# EEZ_SMPS_pre-regulator_r1B1.net
KiCad netlist of a schematic drawn in EAGLE
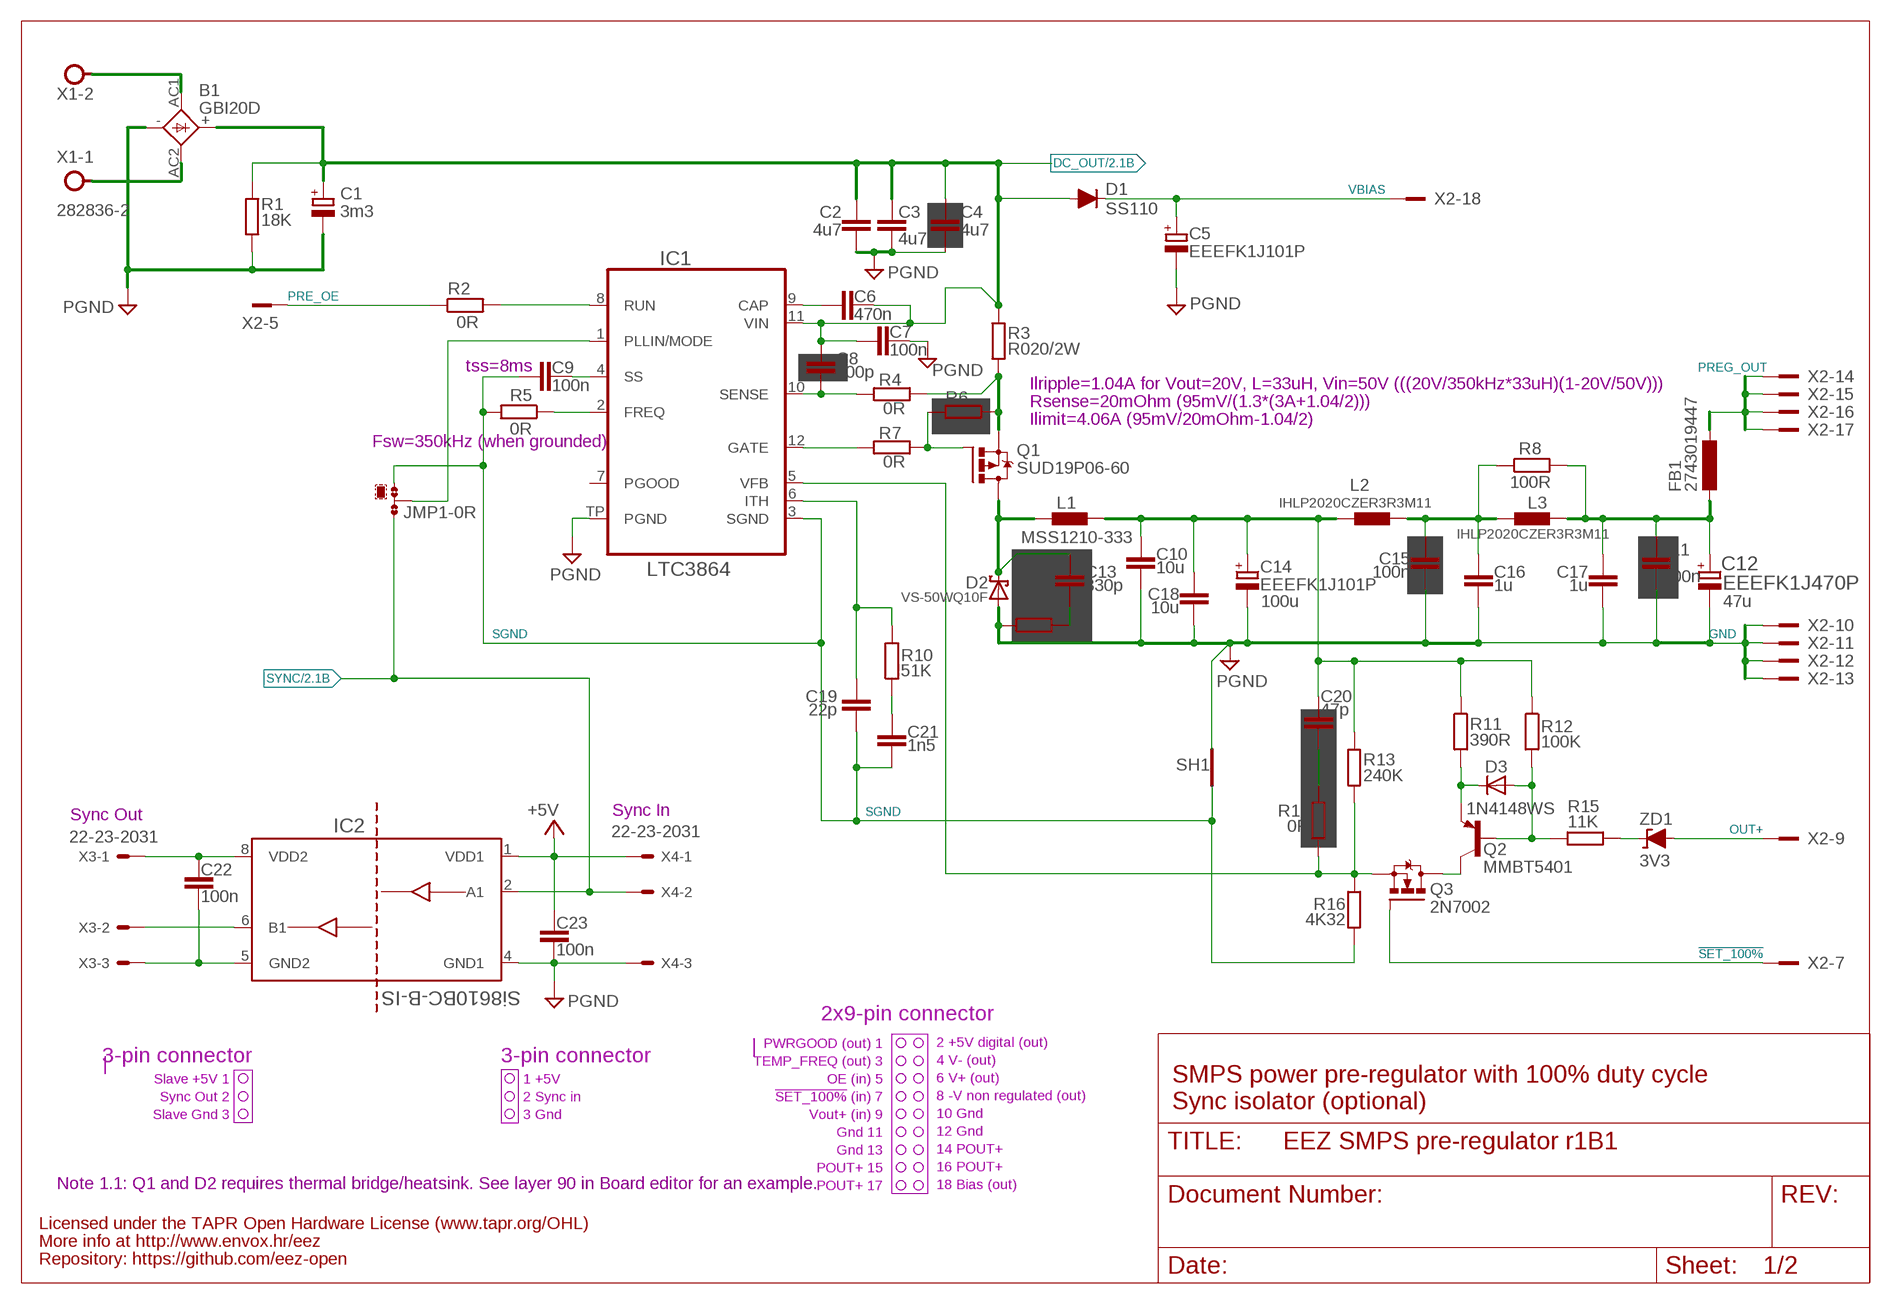
[diagram p0: schematic, sheet 1]
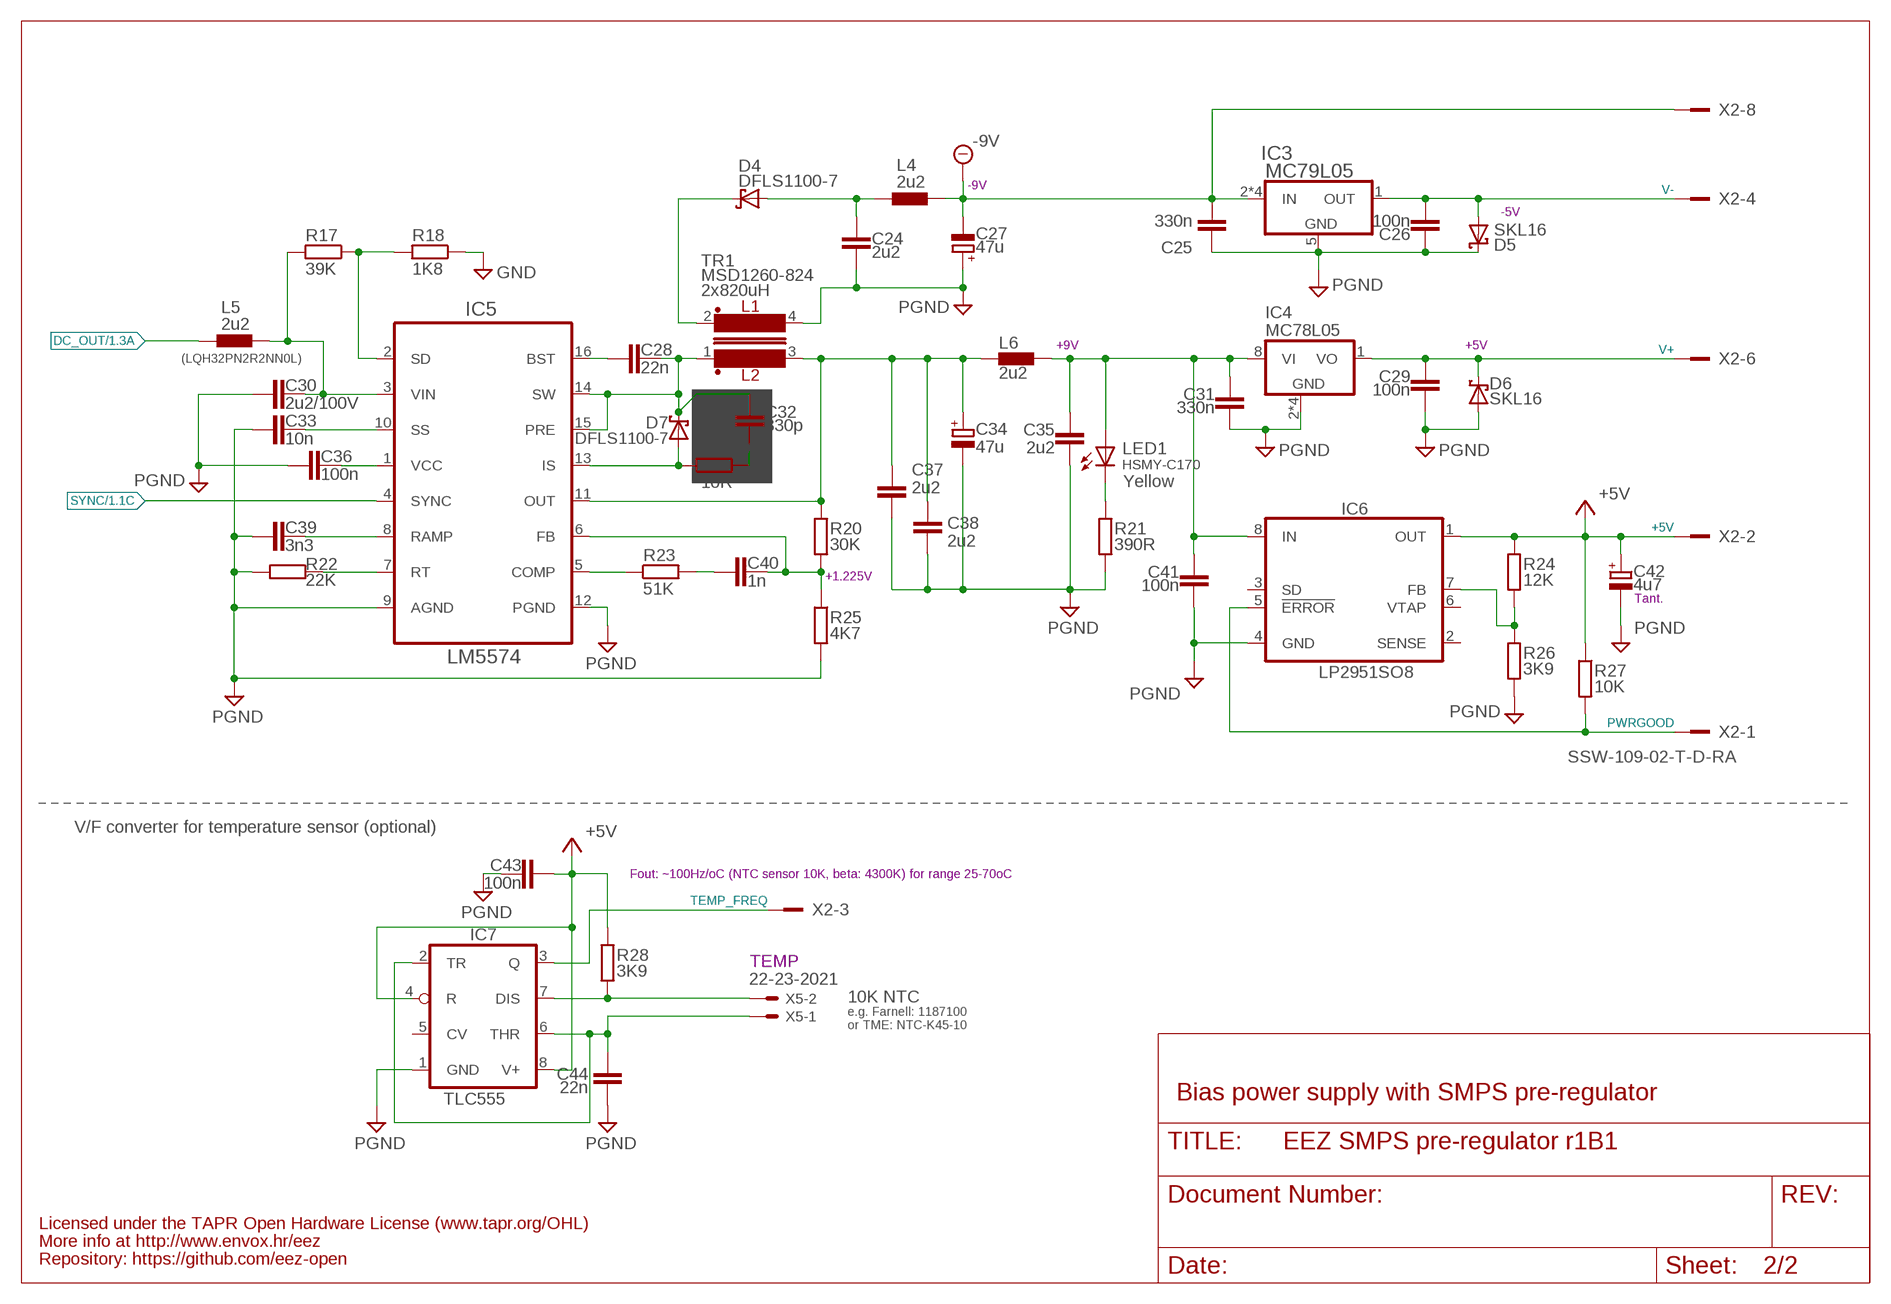
[diagram p1: schematic, sheet 2]

(export (version "E")
  (design (tool "Eeschema 10.0.6"))
  (components
    (comp (ref "C24")
      (value "2u2")
      (footprint "eagle-import:C0805")
      (libsource (lib "eagle-import") (part "C-EUC0805"))
    )
    (comp (ref "C25")
      (value "330n")
      (footprint "eagle-import:C0805")
      (libsource (lib "eagle-import") (part "C-EUC0805"))
    )
    (comp (ref "C26")
      (value "100n")
      (footprint "eagle-import:C0805")
      (libsource (lib "eagle-import") (part "C-EUC0805"))
    )
    (comp (ref "C27")
      (value "47u")
      (footprint "eagle-import:CAPAE660X610N")
      (libsource (lib "eagle-import") (part "ECAPPANASONIC_H"))
    )
    (comp (ref "C28")
      (value "22n")
      (footprint "eagle-import:C0805")
      (libsource (lib "eagle-import") (part "C-EUC0805"))
    )
    (comp (ref "C29")
      (value "100n")
      (footprint "eagle-import:C0805")
      (libsource (lib "eagle-import") (part "C-EUC0805"))
    )
    (comp (ref "C30")
      (value "2u2/100V")
      (footprint "eagle-import:C1210")
      (libsource (lib "eagle-import") (part "C-EUC1210"))
    )
    (comp (ref "C31")
      (value "330n")
      (footprint "eagle-import:C0805")
      (libsource (lib "eagle-import") (part "C-EUC0805"))
    )
    (comp (ref "C32")
      (value "330p")
      (footprint "eagle-import:C0805")
      (libsource (lib "eagle-import") (part "C-EUC0805"))
    )
    (comp (ref "C33")
      (value "10n")
      (footprint "eagle-import:C0805")
      (libsource (lib "eagle-import") (part "C-EUC0805"))
    )
    (comp (ref "C34")
      (value "47u")
      (footprint "eagle-import:CAPAE660X610N")
      (libsource (lib "eagle-import") (part "ECAPPANASONIC_H"))
    )
    (comp (ref "C35")
      (value "2u2")
      (footprint "eagle-import:C0805")
      (libsource (lib "eagle-import") (part "C-EUC0805"))
    )
    (comp (ref "C36")
      (value "100n")
      (footprint "eagle-import:C0805")
      (libsource (lib "eagle-import") (part "C-EUC0805"))
    )
    (comp (ref "C37")
      (value "2u2")
      (footprint "eagle-import:C0805")
      (libsource (lib "eagle-import") (part "C-EUC0805"))
    )
    (comp (ref "C38")
      (value "2u2")
      (footprint "eagle-import:C0805")
      (libsource (lib "eagle-import") (part "C-EUC0805"))
    )
    (comp (ref "C39")
      (value "3n3")
      (footprint "eagle-import:C0805")
      (libsource (lib "eagle-import") (part "C-EUC0805"))
    )
    (comp (ref "C40")
      (value "1n")
      (footprint "eagle-import:C0805")
      (libsource (lib "eagle-import") (part "C-EUC0805"))
    )
    (comp (ref "C41")
      (value "100n")
      (footprint "eagle-import:C0805")
      (libsource (lib "eagle-import") (part "C-EUC0805"))
    )
    (comp (ref "C42")
      (value "4u7")
      (footprint "eagle-import:EC1206")
      (libsource (lib "eagle-import") (part "ECAP1206"))
    )
    (comp (ref "C43")
      (value "100n")
      (footprint "eagle-import:C0603")
      (libsource (lib "eagle-import") (part "C-EUC0603"))
    )
    (comp (ref "C44")
      (value "22n")
      (footprint "eagle-import:C0805")
      (libsource (lib "eagle-import") (part "C-EUC0805"))
    )
    (comp (ref "D4")
      (value "DFLS1100-7")
      (footprint "eagle-import:SOD123")
      (libsource (lib "eagle-import") (part "SCHOTTKYSOD123"))
    )
    (comp (ref "D5")
      (value "SKL16")
      (footprint "eagle-import:SOD123")
      (libsource (lib "eagle-import") (part "SCHOTTKYSOD123"))
    )
    (comp (ref "D6")
      (value "SKL16")
      (footprint "eagle-import:SOD123")
      (libsource (lib "eagle-import") (part "SCHOTTKYSOD123"))
    )
    (comp (ref "D7")
      (value "DFLS1100-7")
      (footprint "eagle-import:SOD123")
      (libsource (lib "eagle-import") (part "SCHOTTKYSOD123"))
    )
    (comp (ref "IC3")
      (value "MC79L05")
      (footprint "eagle-import:SOIC127P600X173-8N")
      (libsource (lib "eagle-import") (part "MC79LXXSOIC"))
    )
    (comp (ref "IC4")
      (value "MC78L05")
      (footprint "eagle-import:SOIC127P600X173-8N")
      (libsource (lib "eagle-import") (part "MC78LXXSOIC8"))
    )
    (comp (ref "IC5")
      (value "LM5574")
      (footprint "eagle-import:SOP65P640X110-16N")
      (fields (field (name "MPN") "LM5574MT"))
      (libsource (lib "eagle-import") (part "LM5574"))
    )
    (comp (ref "IC6")
      (value "LP2951SO8")
      (footprint "eagle-import:SOIC127P600X175-8N")
      (libsource (lib "eagle-import") (part "LP2951SO8"))
    )
    (comp (ref "IC7")
      (value "TLC555")
      (footprint "eagle-import:SOIC127P600X175-8N")
      (libsource (lib "eagle-import") (part "LM555SOIC8"))
    )
    (comp (ref "L4")
      (value "2u2")
      (footprint "eagle-import:L1210")
      (libsource (lib "eagle-import") (part "L1210"))
    )
    (comp (ref "L5")
      (value "2u2")
      (footprint "eagle-import:L1210")
      (libsource (lib "eagle-import") (part "L1210"))
    )
    (comp (ref "L6")
      (value "2u2")
      (footprint "eagle-import:L1210")
      (libsource (lib "eagle-import") (part "L1210"))
    )
    (comp (ref "LED1")
      (value "HSMY-C170")
      (footprint "eagle-import:CHIPLED_0805")
      (libsource (lib "eagle-import") (part "LEDCHIPLED_0805"))
    )
    (comp (ref "R17")
      (value "39K")
      (footprint "eagle-import:R0805")
      (libsource (lib "eagle-import") (part "R-EU_R0805"))
    )
    (comp (ref "R18")
      (value "1K8")
      (footprint "eagle-import:R0805")
      (libsource (lib "eagle-import") (part "R-EU_R0805"))
    )
    (comp (ref "R19")
      (value "10R")
      (footprint "eagle-import:R1206")
      (libsource (lib "eagle-import") (part "R-EU_R1206"))
    )
    (comp (ref "R20")
      (value "30K")
      (footprint "eagle-import:R0805")
      (libsource (lib "eagle-import") (part "R-EU_R0805"))
    )
    (comp (ref "R21")
      (value "390R")
      (footprint "eagle-import:R0805")
      (libsource (lib "eagle-import") (part "R-EU_R0805"))
    )
    (comp (ref "R22")
      (value "22K")
      (footprint "eagle-import:R0805")
      (libsource (lib "eagle-import") (part "R-EU_R0805"))
    )
    (comp (ref "R23")
      (value "51K")
      (footprint "eagle-import:R0805")
      (libsource (lib "eagle-import") (part "R-EU_R0805"))
    )
    (comp (ref "R24")
      (value "12K")
      (footprint "eagle-import:R0805")
      (libsource (lib "eagle-import") (part "R-EU_R0805"))
    )
    (comp (ref "R25")
      (value "4K7")
      (footprint "eagle-import:R0805")
      (libsource (lib "eagle-import") (part "R-EU_R0805"))
    )
    (comp (ref "R26")
      (value "3K9")
      (footprint "eagle-import:R0805")
      (libsource (lib "eagle-import") (part "R-EU_R0805"))
    )
    (comp (ref "R27")
      (value "10K")
      (footprint "eagle-import:R0805")
      (libsource (lib "eagle-import") (part "R-EU_R0805"))
    )
    (comp (ref "R28")
      (value "3K9")
      (footprint "eagle-import:R0805")
      (libsource (lib "eagle-import") (part "R-EU_R0805"))
    )
    (comp (ref "TR1")
      (value "MSD1260-824")
      (footprint "eagle-import:MSD1260")
      (libsource (lib "eagle-import") (part "COILCRAFT_MSD1260INV"))
    )
    (comp (ref "X2")
      (value "SSW-109-02-T-D-RA")
      (footprint "eagle-import:SSW-109-02-T-D-RA")
      (libsource (lib "eagle-import") (part "SSW-109-02-T-D-RA"))
    )
    (comp (ref "X5")
      (value "22-23-2021")
      (footprint "eagle-import:22-23-2021")
      (fields (field (name "MF") "MOLEX"))
      (libsource (lib "eagle-import") (part "22-23-2021"))
    )
    (comp (ref "B1")
      (value "GBI20D")
      (footprint "eagle-import:GBI20")
      (libsource (lib "eagle-import") (part "BRIDGEDIOTEC"))
    )
    (comp (ref "C1")
      (value "3m3")
      (footprint "eagle-import:ECAP10_22.5")
      (libsource (lib "eagle-import") (part "ECAP10G_22.5MM"))
    )
    (comp (ref "C2")
      (value "4u7")
      (footprint "eagle-import:C1210")
      (libsource (lib "eagle-import") (part "C-EUC1210"))
    )
    (comp (ref "C3")
      (value "4u7")
      (footprint "eagle-import:C1210")
      (libsource (lib "eagle-import") (part "C-EUC1210"))
    )
    (comp (ref "C4")
      (value "4u7")
      (footprint "eagle-import:C1210")
      (libsource (lib "eagle-import") (part "C-EUC1210"))
    )
    (comp (ref "C5")
      (value "EEEFK1J101P")
      (footprint "eagle-import:ECAP5_10.5+PANASONIC_F")
      (libsource (lib "eagle-import") (part "ECAP5G_10.5MM_F"))
    )
    (comp (ref "C6")
      (value "470n")
      (footprint "eagle-import:C0805")
      (libsource (lib "eagle-import") (part "C-EUC0805"))
    )
    (comp (ref "C7")
      (value "100n")
      (footprint "eagle-import:C0805")
      (libsource (lib "eagle-import") (part "C-EUC0805"))
    )
    (comp (ref "C8")
      (value "100p")
      (footprint "eagle-import:C0805")
      (libsource (lib "eagle-import") (part "C-EUC0805"))
    )
    (comp (ref "C9")
      (value "100n")
      (footprint "eagle-import:C0805")
      (libsource (lib "eagle-import") (part "C-EUC0805"))
    )
    (comp (ref "C10")
      (value "10u")
      (footprint "eagle-import:C1210")
      (libsource (lib "eagle-import") (part "C-EUC1210"))
    )
    (comp (ref "C11")
      (value "100n")
      (footprint "eagle-import:C0805")
      (libsource (lib "eagle-import") (part "C-EUC0805"))
    )
    (comp (ref "C12")
      (value "EEEFK1J470P")
      (footprint "eagle-import:CAPAE830X1050N")
      (fields (field (name "MPN") "EEE-FK1J470P") (field (name "TOLERANCE") "±20 %"))
      (libsource (lib "eagle-import") (part "EEE--CASE-FFK1J470P"))
    )
    (comp (ref "C13")
      (value "330p")
      (footprint "eagle-import:C0805")
      (libsource (lib "eagle-import") (part "C-EUC0805"))
    )
    (comp (ref "C14")
      (value "EEEFK1J101P")
      (footprint "eagle-import:ECAP5_10.5+PANASONIC_F")
      (libsource (lib "eagle-import") (part "ECAP5G_10.5MM_F"))
    )
    (comp (ref "C15")
      (value "100n")
      (footprint "eagle-import:C0805")
      (libsource (lib "eagle-import") (part "C-EUC0805"))
    )
    (comp (ref "C16")
      (value "1u")
      (footprint "eagle-import:C1206")
      (libsource (lib "eagle-import") (part "C-EUC1206"))
    )
    (comp (ref "C17")
      (value "1u")
      (footprint "eagle-import:C1206")
      (libsource (lib "eagle-import") (part "C-EUC1206"))
    )
    (comp (ref "C18")
      (value "10u")
      (footprint "eagle-import:C1210")
      (libsource (lib "eagle-import") (part "C-EUC1210"))
    )
    (comp (ref "C19")
      (value "22p")
      (footprint "eagle-import:C0805")
      (libsource (lib "eagle-import") (part "C-EUC0805"))
    )
    (comp (ref "C20")
      (value "47p")
      (footprint "eagle-import:C0805")
      (libsource (lib "eagle-import") (part "C-EUC0805"))
    )
    (comp (ref "C21")
      (value "1n5")
      (footprint "eagle-import:C0805")
      (libsource (lib "eagle-import") (part "C-EUC0805"))
    )
    (comp (ref "C22")
      (value "100n")
      (footprint "eagle-import:C0603")
      (libsource (lib "eagle-import") (part "C-EUC0603"))
    )
    (comp (ref "C23")
      (value "100n")
      (footprint "eagle-import:C0603")
      (libsource (lib "eagle-import") (part "C-EUC0603"))
    )
    (comp (ref "D1")
      (value "SS110")
      (footprint "eagle-import:DO214AA")
      (libsource (lib "eagle-import") (part "DIODEDO214AA"))
    )
    (comp (ref "D2")
      (value "VS-50WQ10F")
      (footprint "eagle-import:TO252@1")
      (libsource (lib "eagle-import") (part "SCHOTTKYTO252"))
    )
    (comp (ref "D3")
      (value "1N4148WS")
      (footprint "eagle-import:SOD323-W")
      (libsource (lib "eagle-import") (part "DIODE-SOD323-W"))
    )
    (comp (ref "FB1")
      (value "2743019447")
      (footprint "eagle-import:L1812")
      (libsource (lib "eagle-import") (part "L-EUL1812"))
    )
    (comp (ref "IC1")
      (value "LTC3864")
      (footprint "eagle-import:LTC_05-08-1666")
      (libsource (lib "eagle-import") (part "LTC3864"))
    )
    (comp (ref "IC2")
      (value "Si8610BC-B-IS")
      (footprint "eagle-import:SOIC127P600X173-8N")
      (libsource (lib "eagle-import") (part "SI8610"))
    )
    (comp (ref "JMP1")
      (value "0R-JUMPA")
      (footprint "eagle-import:A0R-JMP")
      (libsource (lib "eagle-import") (part "0R-JUMPA"))
    )
    (comp (ref "L1")
      (value "MSS1210-333")
      (footprint "eagle-import:MSS1210")
      (libsource (lib "eagle-import") (part "COILCRAFT_MSS1210"))
    )
    (comp (ref "L2")
      (value "IHLP2020CZER3R3M11")
      (footprint "eagle-import:IHLP-2020BZ-11")
      (libsource (lib "eagle-import") (part "IHLP-2020BZ-11"))
    )
    (comp (ref "L3")
      (value "IHLP2020CZER3R3M11")
      (footprint "eagle-import:IHLP-2020BZ-11")
      (libsource (lib "eagle-import") (part "IHLP-2020BZ-11"))
    )
    (comp (ref "Q1")
      (value "SUD19P06-60")
      (footprint "eagle-import:TO229P990X239-3N")
      (libsource (lib "eagle-import") (part "P-MOSFETDPAK"))
    )
    (comp (ref "Q2")
      (value "MMBT5401")
      (footprint "eagle-import:SOT23-BEC")
      (libsource (lib "eagle-import") (part "-PNP-SOT23-BECBC857B"))
    )
    (comp (ref "Q3")
      (value "2N7002")
      (footprint "eagle-import:SOT103P240X110-3N")
      (fields (field (name "MPN") "2N7002-7-F"))
      (libsource (lib "eagle-import") (part "2N7002"))
    )
    (comp (ref "R1")
      (value "18K")
      (footprint "eagle-import:R1206")
      (libsource (lib "eagle-import") (part "R-EU_R1206"))
    )
    (comp (ref "R2")
      (value "0R")
      (footprint "eagle-import:R0805")
      (libsource (lib "eagle-import") (part "R-EU_R0805"))
    )
    (comp (ref "R3")
      (value "R020/2W")
      (footprint "eagle-import:R2512")
      (libsource (lib "eagle-import") (part "R-EU_R2512"))
    )
    (comp (ref "R4")
      (value "0R")
      (footprint "eagle-import:R0805")
      (libsource (lib "eagle-import") (part "R-EU_R0805"))
    )
    (comp (ref "R5")
      (value "0R")
      (footprint "eagle-import:R0805")
      (libsource (lib "eagle-import") (part "R-EU_R0805"))
    )
    (comp (ref "R6")
      (value "100K")
      (footprint "eagle-import:R0805")
      (libsource (lib "eagle-import") (part "R-EU_R0805"))
    )
    (comp (ref "R7")
      (value "0R")
      (footprint "eagle-import:R0805")
      (libsource (lib "eagle-import") (part "R-EU_R0805"))
    )
    (comp (ref "R8")
      (value "100R")
      (footprint "eagle-import:R0805")
      (libsource (lib "eagle-import") (part "R-EU_R0805"))
    )
    (comp (ref "R9")
      (value "10R")
      (footprint "eagle-import:R1206")
      (libsource (lib "eagle-import") (part "R-EU_R1206"))
    )
    (comp (ref "R10")
      (value "51K")
      (footprint "eagle-import:R0805")
      (libsource (lib "eagle-import") (part "R-EU_R0805"))
    )
    (comp (ref "R11")
      (value "390R")
      (footprint "eagle-import:R0805")
      (libsource (lib "eagle-import") (part "R-EU_R0805"))
    )
    (comp (ref "R12")
      (value "100K")
      (footprint "eagle-import:R0805")
      (libsource (lib "eagle-import") (part "R-EU_R0805"))
    )
    (comp (ref "R13")
      (value "240K")
      (footprint "eagle-import:R0805")
      (libsource (lib "eagle-import") (part "R-EU_R0805"))
    )
    (comp (ref "R14")
      (value "0R")
      (footprint "eagle-import:R0805")
      (libsource (lib "eagle-import") (part "R-EU_R0805"))
    )
    (comp (ref "R15")
      (value "11K")
      (footprint "eagle-import:R0805")
      (libsource (lib "eagle-import") (part "R-EU_R0805"))
    )
    (comp (ref "R16")
      (value "4K32")
      (footprint "eagle-import:R0805")
      (libsource (lib "eagle-import") (part "R-EU_R0805"))
    )
    (comp (ref "SH1")
      (value "Sgnd to Pgnd short")
      (footprint "eagle-import:SHORT_NOHOLE")
      (libsource (lib "eagle-import") (part "SHORTNOHOLE"))
    )
    (comp (ref "X1")
      (value "282836-2")
      (footprint "eagle-import:TBLOCK5.0_2")
      (libsource (lib "eagle-import") (part "TBLOCK5.0_2A"))
    )
    (comp (ref "X3")
      (value "22-23-2031")
      (footprint "eagle-import:22-23-2031")
      (fields
        (field (name "MF") "MOLEX")
        (field (name "MF_1") "MOLEX")
        (field (name "MPN") "22-23-2031")
        (field (name "OC_FARNELL") "1462950")
        (field (name "OC_NEWARK") "30C0862")
      )
      (libsource (lib "eagle-import") (part "22-23-2031"))
    )
    (comp (ref "X4")
      (value "22-23-2031")
      (footprint "eagle-import:22-23-2031")
      (fields
        (field (name "MF") "MOLEX")
        (field (name "MF_1") "MOLEX")
        (field (name "MPN") "22-23-2031")
        (field (name "OC_FARNELL") "1462950")
        (field (name "OC_NEWARK") "30C0862")
      )
      (libsource (lib "eagle-import") (part "22-23-2031"))
    )
    (comp (ref "ZD1")
      (value "3V3")
      (footprint "eagle-import:MINIMELF")
      (libsource (lib "eagle-import") (part "ZENER-DIODEMINIMELF"))
    )
  )
  (nets
    (net (code "1") (name "+5V") (class "Default")
      (node (ref "C23") (pin "1") (pinfunction "1_1") (pintype "passive"))
      (node (ref "C42") (pin "+") (pinfunction "+_+") (pintype "passive"))
      (node (ref "C43") (pin "1") (pinfunction "1_1") (pintype "passive"))
      (node (ref "IC2") (pin "1") (pinfunction "VDD1_1") (pintype "power_in"))
      (node (ref "IC6") (pin "1") (pinfunction "OUT_1") (pintype "output"))
      (node (ref "IC7") (pin "4") (pinfunction "R_4") (pintype "input"))
      (node (ref "IC7") (pin "8") (pinfunction "V+_8") (pintype "power_in"))
      (node (ref "R24") (pin "1") (pinfunction "1_1") (pintype "passive"))
      (node (ref "R27") (pin "1") (pinfunction "1_1") (pintype "passive"))
      (node (ref "R28") (pin "2") (pinfunction "2_2") (pintype "passive"))
      (node (ref "X2") (pin "2") (pinfunction "1_2") (pintype "passive"))
      (node (ref "X4") (pin "1") (pinfunction "S_1") (pintype "passive"))
    )
    (net (code "2") (name "-9V") (class "Default")
      (node (ref "C25") (pin "2") (pinfunction "2_2") (pintype "passive"))
      (node (ref "C27") (pin "2") (pinfunction "-_2") (pintype "passive"))
      (node (ref "IC3") (pin "2") (pinfunction "IN_2") (pintype "input"))
      (node (ref "IC3") (pin "3") (pinfunction "IN_3") (pintype "input"))
      (node (ref "IC3") (pin "6") (pinfunction "IN_6") (pintype "input"))
      (node (ref "IC3") (pin "7") (pinfunction "IN_7") (pintype "input"))
      (node (ref "L4") (pin "2") (pinfunction "2_2") (pintype "passive"))
      (node (ref "X2") (pin "8") (pinfunction "1_8") (pintype "passive"))
    )
    (net (code "3") (name "DC_OUT") (class "Default")
      (node (ref "B1") (pin "+") (pinfunction "+_+") (pintype "passive"))
      (node (ref "C1") (pin "+") (pinfunction "+_+") (pintype "passive"))
      (node (ref "C2") (pin "1") (pinfunction "1_1") (pintype "passive"))
      (node (ref "C3") (pin "1") (pinfunction "1_1") (pintype "passive"))
      (node (ref "C4") (pin "1") (pinfunction "1_1") (pintype "passive"))
      (node (ref "C6") (pin "2") (pinfunction "2_2") (pintype "passive"))
      (node (ref "C7") (pin "1") (pinfunction "1_1") (pintype "passive"))
      (node (ref "C8") (pin "1") (pinfunction "1_1") (pintype "passive"))
      (node (ref "D1") (pin "A") (pinfunction "A_A") (pintype "passive"))
      (node (ref "IC1") (pin "11") (pinfunction "VIN_11") (pintype "passive"))
      (node (ref "L5") (pin "1") (pinfunction "1_1") (pintype "passive"))
      (node (ref "R1") (pin "1") (pinfunction "1_1") (pintype "passive"))
      (node (ref "R3") (pin "1") (pinfunction "1_1") (pintype "passive"))
    )
    (net (code "4") (name "GND") (class "Default")
      (node (ref "B1") (pin "-") (pinfunction "-_-") (pintype "passive"))
      (node (ref "C1") (pin "-") (pinfunction "-_-") (pintype "passive"))
      (node (ref "C10") (pin "2") (pinfunction "2_2") (pintype "passive"))
      (node (ref "C11") (pin "2") (pinfunction "2_2") (pintype "passive"))
      (node (ref "C12") (pin "2") (pinfunction "2_2") (pintype "passive"))
      (node (ref "C14") (pin "-") (pinfunction "-_-") (pintype "passive"))
      (node (ref "C14") (pin "-.1") (pinfunction "-_-.1") (pintype "passive"))
      (node (ref "C15") (pin "1") (pinfunction "1_1") (pintype "passive"))
      (node (ref "C16") (pin "2") (pinfunction "2_2") (pintype "passive"))
      (node (ref "C17") (pin "2") (pinfunction "2_2") (pintype "passive"))
      (node (ref "C18") (pin "2") (pinfunction "2_2") (pintype "passive"))
      (node (ref "C2") (pin "2") (pinfunction "2_2") (pintype "passive"))
      (node (ref "C23") (pin "2") (pinfunction "2_2") (pintype "passive"))
      (node (ref "C24") (pin "2") (pinfunction "2_2") (pintype "passive"))
      (node (ref "C25") (pin "1") (pinfunction "1_1") (pintype "passive"))
      (node (ref "C26") (pin "1") (pinfunction "1_1") (pintype "passive"))
      (node (ref "C27") (pin "1") (pinfunction "+_1") (pintype "passive"))
      (node (ref "C29") (pin "2") (pinfunction "2_2") (pintype "passive"))
      (node (ref "C3") (pin "2") (pinfunction "2_2") (pintype "passive"))
      (node (ref "C30") (pin "2") (pinfunction "2_2") (pintype "passive"))
      (node (ref "C31") (pin "2") (pinfunction "2_2") (pintype "passive"))
      (node (ref "C33") (pin "2") (pinfunction "2_2") (pintype "passive"))
      (node (ref "C34") (pin "2") (pinfunction "-_2") (pintype "passive"))
      (node (ref "C35") (pin "2") (pinfunction "2_2") (pintype "passive"))
      (node (ref "C36") (pin "1") (pinfunction "1_1") (pintype "passive"))
      (node (ref "C37") (pin "2") (pinfunction "2_2") (pintype "passive"))
      (node (ref "C38") (pin "2") (pinfunction "2_2") (pintype "passive"))
      (node (ref "C39") (pin "1") (pinfunction "1_1") (pintype "passive"))
      (node (ref "C4") (pin "2") (pinfunction "2_2") (pintype "passive"))
      (node (ref "C41") (pin "2") (pinfunction "2_2") (pintype "passive"))
      (node (ref "C42") (pin "-") (pinfunction "-_-") (pintype "passive"))
      (node (ref "C43") (pin "2") (pinfunction "2_2") (pintype "passive"))
      (node (ref "C44") (pin "1") (pinfunction "1_1") (pintype "passive"))
      (node (ref "C5") (pin "-") (pinfunction "-_-") (pintype "passive"))
      (node (ref "C5") (pin "-.1") (pinfunction "-_-.1") (pintype "passive"))
      (node (ref "C7") (pin "2") (pinfunction "2_2") (pintype "passive"))
      (node (ref "D2") (pin "1") (pinfunction "A_1") (pintype "passive"))
      (node (ref "D2") (pin "2") (pinfunction "A_2") (pintype "passive"))
      (node (ref "D5") (pin "C") (pinfunction "C_C") (pintype "passive"))
      (node (ref "D6") (pin "A") (pinfunction "A_A") (pintype "passive"))
      (node (ref "IC1") (pin "TP") (pinfunction "PGND_TP") (pintype "passive"))
      (node (ref "IC2") (pin "4") (pinfunction "GND1_4") (pintype "power_in"))
      (node (ref "IC3") (pin "5") (pinfunction "GND_5") (pintype "passive"))
      (node (ref "IC4") (pin "2") (pinfunction "GND_2") (pintype "passive"))
      (node (ref "IC4") (pin "3") (pinfunction "GND_3") (pintype "passive"))
      (node (ref "IC4") (pin "6") (pinfunction "GND_6") (pintype "passive"))
      (node (ref "IC4") (pin "7") (pinfunction "GND_7") (pintype "passive"))
      (node (ref "IC5") (pin "12") (pinfunction "PGND_12") (pintype "passive"))
      (node (ref "IC5") (pin "9") (pinfunction "AGND_9") (pintype "passive"))
      (node (ref "IC6") (pin "4") (pinfunction "GND_4") (pintype "passive"))
      (node (ref "IC7") (pin "1") (pinfunction "GND_1") (pintype "power_in"))
      (node (ref "R1") (pin "2") (pinfunction "2_2") (pintype "passive"))
      (node (ref "R18") (pin "1") (pinfunction "1_1") (pintype "passive"))
      (node (ref "R21") (pin "2") (pinfunction "2_2") (pintype "passive"))
      (node (ref "R22") (pin "2") (pinfunction "2_2") (pintype "passive"))
      (node (ref "R25") (pin "2") (pinfunction "2_2") (pintype "passive"))
      (node (ref "R26") (pin "2") (pinfunction "2_2") (pintype "passive"))
      (node (ref "R9") (pin "1") (pinfunction "1_1") (pintype "passive"))
      (node (ref "SH1") (pin "P$2") (pinfunction "GND_B_P$2") (pintype "bidirectional"))
      (node (ref "TR1") (pin "4") (pinfunction "4_4") (pintype "passive"))
      (node (ref "X2") (pin "10") (pinfunction "1_10") (pintype "passive"))
      (node (ref "X2") (pin "11") (pinfunction "1_11") (pintype "passive"))
      (node (ref "X2") (pin "12") (pinfunction "1_12") (pintype "passive"))
      (node (ref "X2") (pin "13") (pinfunction "1_13") (pintype "passive"))
      (node (ref "X4") (pin "3") (pinfunction "S_3") (pintype "passive"))
    )
    (net (code "5") (name "Net-(B1-PadAC2)") (class "Default")
      (node (ref "B1") (pin "AC2") (pinfunction "AC2_AC2") (pintype "passive"))
      (node (ref "X1") (pin "1") (pinfunction "1_1") (pintype "bidirectional"))
    )
    (net (code "6") (name "Net-(C10-Pad1)") (class "Default")
      (node (ref "C10") (pin "1") (pinfunction "1_1") (pintype "passive"))
      (node (ref "C14") (pin "+") (pinfunction "+_+") (pintype "passive"))
      (node (ref "C14") (pin "+.1") (pinfunction "+_+.1") (pintype "passive"))
      (node (ref "C18") (pin "1") (pinfunction "1_1") (pintype "passive"))
      (node (ref "C20") (pin "1") (pinfunction "1_1") (pintype "passive"))
      (node (ref "L1") (pin "2") (pinfunction "2_2") (pintype "passive"))
      (node (ref "L2") (pin "1") (pinfunction "1_1") (pintype "passive"))
      (node (ref "R11") (pin "1") (pinfunction "1_1") (pintype "passive"))
      (node (ref "R12") (pin "1") (pinfunction "1_1") (pintype "passive"))
      (node (ref "R13") (pin "1") (pinfunction "1_1") (pintype "passive"))
    )
    (net (code "7") (name "Net-(C11-Pad1)") (class "Default")
      (node (ref "C11") (pin "1") (pinfunction "1_1") (pintype "passive"))
      (node (ref "C12") (pin "1") (pinfunction "1_1") (pintype "passive"))
      (node (ref "C17") (pin "1") (pinfunction "1_1") (pintype "passive"))
      (node (ref "FB1") (pin "1") (pinfunction "1_1") (pintype "passive"))
      (node (ref "L3") (pin "2") (pinfunction "2_2") (pintype "passive"))
      (node (ref "R8") (pin "2") (pinfunction "2_2") (pintype "passive"))
    )
    (net (code "8") (name "Net-(C13-Pad2)") (class "Default")
      (node (ref "C13") (pin "2") (pinfunction "2_2") (pintype "passive"))
      (node (ref "R9") (pin "2") (pinfunction "2_2") (pintype "passive"))
    )
    (net (code "9") (name "Net-(C15-Pad2)") (class "Default")
      (node (ref "C15") (pin "2") (pinfunction "2_2") (pintype "passive"))
      (node (ref "C16") (pin "1") (pinfunction "1_1") (pintype "passive"))
      (node (ref "L2") (pin "2") (pinfunction "2_2") (pintype "passive"))
      (node (ref "L3") (pin "1") (pinfunction "1_1") (pintype "passive"))
      (node (ref "R8") (pin "1") (pinfunction "1_1") (pintype "passive"))
    )
    (net (code "10") (name "Net-(C20-Pad2)") (class "Default")
      (node (ref "C20") (pin "2") (pinfunction "2_2") (pintype "passive"))
      (node (ref "R14") (pin "2") (pinfunction "2_2") (pintype "passive"))
    )
    (net (code "11") (name "Net-(C21-Pad1)") (class "Default")
      (node (ref "C21") (pin "1") (pinfunction "1_1") (pintype "passive"))
      (node (ref "R10") (pin "1") (pinfunction "1_1") (pintype "passive"))
    )
    (net (code "12") (name "Net-(C24-Pad1)") (class "Default")
      (node (ref "C24") (pin "1") (pinfunction "1_1") (pintype "passive"))
      (node (ref "D4") (pin "A") (pinfunction "A_A") (pintype "passive"))
      (node (ref "L4") (pin "1") (pinfunction "1_1") (pintype "passive"))
    )
    (net (code "13") (name "Net-(C32-Pad2)") (class "Default")
      (node (ref "C32") (pin "2") (pinfunction "2_2") (pintype "passive"))
      (node (ref "R19") (pin "2") (pinfunction "2_2") (pintype "passive"))
    )
    (net (code "14") (name "Net-(C34-+)") (class "Default")
      (node (ref "C34") (pin "1") (pinfunction "+_1") (pintype "passive"))
      (node (ref "C37") (pin "1") (pinfunction "1_1") (pintype "passive"))
      (node (ref "C38") (pin "1") (pinfunction "1_1") (pintype "passive"))
      (node (ref "IC5") (pin "11") (pinfunction "OUT_11") (pintype "output"))
      (node (ref "L6") (pin "1") (pinfunction "1_1") (pintype "passive"))
      (node (ref "R20") (pin "1") (pinfunction "1_1") (pintype "passive"))
      (node (ref "TR1") (pin "3") (pinfunction "3_3") (pintype "passive"))
    )
    (net (code "15") (name "Net-(C40-Pad2)") (class "Default")
      (node (ref "C40") (pin "2") (pinfunction "2_2") (pintype "passive"))
      (node (ref "R23") (pin "2") (pinfunction "2_2") (pintype "passive"))
    )
    (net (code "16") (name "Net-(D2-C)") (class "Default")
      (node (ref "C13") (pin "1") (pinfunction "1_1") (pintype "passive"))
      (node (ref "D2") (pin "3") (pinfunction "C_3") (pintype "passive"))
      (node (ref "L1") (pin "1") (pinfunction "1_1") (pintype "passive"))
      (node (ref "Q1") (pin "2") (pinfunction "D_2") (pintype "passive"))
    )
    (net (code "17") (name "Net-(D3-PadA)") (class "Default")
      (node (ref "D3") (pin "A") (pinfunction "A_A") (pintype "passive"))
      (node (ref "Q2") (pin "B") (pinfunction "B_B") (pintype "passive"))
      (node (ref "R12") (pin "2") (pinfunction "2_2") (pintype "passive"))
      (node (ref "R15") (pin "1") (pinfunction "1_1") (pintype "passive"))
    )
    (net (code "18") (name "Net-(D3-PadC)") (class "Default")
      (node (ref "D3") (pin "C") (pinfunction "C_C") (pintype "passive"))
      (node (ref "Q2") (pin "E") (pinfunction "E_E") (pintype "passive"))
      (node (ref "R11") (pin "2") (pinfunction "2_2") (pintype "passive"))
    )
    (net (code "19") (name "Net-(D4-PadC)") (class "Default")
      (node (ref "D4") (pin "C") (pinfunction "C_C") (pintype "passive"))
      (node (ref "TR1") (pin "2") (pinfunction "2_2") (pintype "passive"))
    )
    (net (code "20") (name "Net-(IC1-CAP)") (class "Default")
      (node (ref "C6") (pin "1") (pinfunction "1_1") (pintype "passive"))
      (node (ref "IC1") (pin "9") (pinfunction "CAP_9") (pintype "passive"))
    )
    (net (code "21") (name "Net-(IC1-FREQ)") (class "Default")
      (node (ref "IC1") (pin "2") (pinfunction "FREQ_2") (pintype "input"))
      (node (ref "R5") (pin "1") (pinfunction "1_1") (pintype "passive"))
    )
    (net (code "22") (name "Net-(IC1-GATE)") (class "Default")
      (node (ref "IC1") (pin "12") (pinfunction "GATE_12") (pintype "output"))
      (node (ref "R7") (pin "2") (pinfunction "2_2") (pintype "passive"))
    )
    (net (code "23") (name "Net-(IC1-ITH)") (class "Default")
      (node (ref "C19") (pin "1") (pinfunction "1_1") (pintype "passive"))
      (node (ref "IC1") (pin "6") (pinfunction "ITH_6") (pintype "bidirectional"))
      (node (ref "R10") (pin "2") (pinfunction "2_2") (pintype "passive"))
    )
    (net (code "24") (name "Net-(IC1-PLLIN{slash}MODE)") (class "Default")
      (node (ref "IC1") (pin "1") (pinfunction "PLLIN/MODE_1") (pintype "input"))
      (node (ref "JMP1") (pin "2") (pinfunction "2_2") (pintype "passive"))
    )
    (net (code "25") (name "Net-(IC1-RUN)") (class "Default")
      (node (ref "IC1") (pin "8") (pinfunction "RUN_8") (pintype "input"))
      (node (ref "R2") (pin "2") (pinfunction "2_2") (pintype "passive"))
    )
    (net (code "26") (name "Net-(IC1-SENSE)") (class "Default")
      (node (ref "C8") (pin "2") (pinfunction "2_2") (pintype "passive"))
      (node (ref "IC1") (pin "10") (pinfunction "SENSE_10") (pintype "input"))
      (node (ref "R4") (pin "2") (pinfunction "2_2") (pintype "passive"))
    )
    (net (code "27") (name "Net-(IC1-SS)") (class "Default")
      (node (ref "C9") (pin "2") (pinfunction "2_2") (pintype "passive"))
      (node (ref "IC1") (pin "4") (pinfunction "SS_4") (pintype "input"))
    )
    (net (code "28") (name "Net-(IC1-VFB)") (class "Default")
      (node (ref "IC1") (pin "5") (pinfunction "VFB_5") (pintype "input"))
      (node (ref "Q3") (pin "2") (pinfunction "S_2") (pintype "passive"))
      (node (ref "R13") (pin "2") (pinfunction "2_2") (pintype "passive"))
      (node (ref "R14") (pin "1") (pinfunction "1_1") (pintype "passive"))
      (node (ref "R16") (pin "1") (pinfunction "1_1") (pintype "passive"))
    )
    (net (code "29") (name "Net-(IC2-B1)") (class "Default")
      (node (ref "IC2") (pin "6") (pinfunction "B1_6") (pintype "output"))
      (node (ref "X3") (pin "2") (pinfunction "S_2") (pintype "passive"))
    )
    (net (code "30") (name "Net-(IC2-GND2)") (class "Default")
      (node (ref "C22") (pin "2") (pinfunction "2_2") (pintype "passive"))
      (node (ref "IC2") (pin "5") (pinfunction "GND2_5") (pintype "power_in"))
      (node (ref "X3") (pin "3") (pinfunction "S_3") (pintype "passive"))
    )
    (net (code "31") (name "Net-(IC2-VDD2)") (class "Default")
      (node (ref "C22") (pin "1") (pinfunction "1_1") (pintype "passive"))
      (node (ref "IC2") (pin "8") (pinfunction "VDD2_8") (pintype "power_in"))
      (node (ref "X3") (pin "1") (pinfunction "S_1") (pintype "passive"))
    )
    (net (code "32") (name "Net-(IC4-VI)") (class "Default")
      (node (ref "C31") (pin "1") (pinfunction "1_1") (pintype "passive"))
      (node (ref "C35") (pin "1") (pinfunction "1_1") (pintype "passive"))
      (node (ref "C41") (pin "1") (pinfunction "1_1") (pintype "passive"))
      (node (ref "IC4") (pin "8") (pinfunction "VI_8") (pintype "input"))
      (node (ref "IC6") (pin "8") (pinfunction "IN_8") (pintype "power_in"))
      (node (ref "L6") (pin "2") (pinfunction "2_2") (pintype "passive"))
      (node (ref "LED1") (pin "A") (pinfunction "A_A") (pintype "passive"))
    )
    (net (code "33") (name "Net-(IC5-BST)") (class "Default")
      (node (ref "C28") (pin "2") (pinfunction "2_2") (pintype "passive"))
      (node (ref "IC5") (pin "16") (pinfunction "BST_16") (pintype "input"))
    )
    (net (code "34") (name "Net-(IC5-COMP)") (class "Default")
      (node (ref "IC5") (pin "5") (pinfunction "COMP_5") (pintype "input"))
      (node (ref "R23") (pin "1") (pinfunction "1_1") (pintype "passive"))
    )
    (net (code "35") (name "Net-(IC5-FB)") (class "Default")
      (node (ref "C40") (pin "1") (pinfunction "1_1") (pintype "passive"))
      (node (ref "IC5") (pin "6") (pinfunction "FB_6") (pintype "input"))
      (node (ref "R20") (pin "2") (pinfunction "2_2") (pintype "passive"))
      (node (ref "R25") (pin "1") (pinfunction "1_1") (pintype "passive"))
    )
    (net (code "36") (name "Net-(IC5-IS)") (class "Default")
      (node (ref "D7") (pin "A") (pinfunction "A_A") (pintype "passive"))
      (node (ref "IC5") (pin "13") (pinfunction "IS_13") (pintype "input"))
      (node (ref "R19") (pin "1") (pinfunction "1_1") (pintype "passive"))
    )
    (net (code "37") (name "Net-(IC5-PRE)") (class "Default")
      (node (ref "C28") (pin "1") (pinfunction "1_1") (pintype "passive"))
      (node (ref "C32") (pin "1") (pinfunction "1_1") (pintype "passive"))
      (node (ref "D7") (pin "C") (pinfunction "C_C") (pintype "passive"))
      (node (ref "IC5") (pin "14") (pinfunction "SW_14") (pintype "output"))
      (node (ref "IC5") (pin "15") (pinfunction "PRE_15") (pintype "input"))
      (node (ref "TR1") (pin "1") (pinfunction "1_1") (pintype "passive"))
    )
    (net (code "38") (name "Net-(IC5-RAMP)") (class "Default")
      (node (ref "C39") (pin "2") (pinfunction "2_2") (pintype "passive"))
      (node (ref "IC5") (pin "8") (pinfunction "RAMP_8") (pintype "input"))
    )
    (net (code "39") (name "Net-(IC5-RT)") (class "Default")
      (node (ref "IC5") (pin "7") (pinfunction "RT_7") (pintype "input"))
      (node (ref "R22") (pin "1") (pinfunction "1_1") (pintype "passive"))
    )
    (net (code "40") (name "Net-(IC5-SD)") (class "Default")
      (node (ref "IC5") (pin "2") (pinfunction "SD_2") (pintype "input"))
      (node (ref "R17") (pin "1") (pinfunction "1_1") (pintype "passive"))
      (node (ref "R18") (pin "2") (pinfunction "2_2") (pintype "passive"))
    )
    (net (code "41") (name "Net-(IC5-SS)") (class "Default")
      (node (ref "C33") (pin "1") (pinfunction "1_1") (pintype "passive"))
      (node (ref "IC5") (pin "10") (pinfunction "SS_10") (pintype "input"))
    )
    (net (code "42") (name "Net-(IC5-VCC)") (class "Default")
      (node (ref "C36") (pin "2") (pinfunction "2_2") (pintype "passive"))
      (node (ref "IC5") (pin "1") (pinfunction "VCC_1") (pintype "power_in"))
    )
    (net (code "43") (name "Net-(IC5-VIN)") (class "Default")
      (node (ref "C30") (pin "1") (pinfunction "1_1") (pintype "passive"))
      (node (ref "IC5") (pin "3") (pinfunction "VIN_3") (pintype "input"))
      (node (ref "L5") (pin "2") (pinfunction "2_2") (pintype "passive"))
      (node (ref "R17") (pin "2") (pinfunction "2_2") (pintype "passive"))
    )
    (net (code "44") (name "Net-(IC6-FB)") (class "Default")
      (node (ref "IC6") (pin "7") (pinfunction "FB_7") (pintype "input"))
      (node (ref "R24") (pin "2") (pinfunction "2_2") (pintype "passive"))
      (node (ref "R26") (pin "1") (pinfunction "1_1") (pintype "passive"))
    )
    (net (code "45") (name "Net-(IC7-DIS)") (class "Default")
      (node (ref "IC7") (pin "7") (pinfunction "DIS_7") (pintype "input"))
      (node (ref "R28") (pin "1") (pinfunction "1_1") (pintype "passive"))
      (node (ref "X5") (pin "2") (pinfunction "S_2") (pintype "passive"))
    )
    (net (code "46") (name "Net-(IC7-THR)") (class "Default")
      (node (ref "C44") (pin "2") (pinfunction "2_2") (pintype "passive"))
      (node (ref "IC7") (pin "2") (pinfunction "TR_2") (pintype "input"))
      (node (ref "IC7") (pin "6") (pinfunction "THR_6") (pintype "input"))
      (node (ref "X5") (pin "1") (pinfunction "S_1") (pintype "passive"))
    )
    (net (code "47") (name "Net-(LED1-PadC)") (class "Default")
      (node (ref "LED1") (pin "C") (pinfunction "C_C") (pintype "passive"))
      (node (ref "R21") (pin "1") (pinfunction "1_1") (pintype "passive"))
    )
    (net (code "48") (name "Net-(Q1-G)") (class "Default")
      (node (ref "Q1") (pin "1") (pinfunction "G_1") (pintype "passive"))
      (node (ref "R6") (pin "1") (pinfunction "1_1") (pintype "passive"))
      (node (ref "R7") (pin "1") (pinfunction "1_1") (pintype "passive"))
    )
    (net (code "49") (name "Net-(Q1-S)") (class "Default")
      (node (ref "Q1") (pin "3") (pinfunction "S_3") (pintype "passive"))
      (node (ref "R3") (pin "2") (pinfunction "2_2") (pintype "passive"))
      (node (ref "R4") (pin "1") (pinfunction "1_1") (pintype "passive"))
      (node (ref "R6") (pin "2") (pinfunction "2_2") (pintype "passive"))
    )
    (net (code "50") (name "Net-(Q3-D)") (class "Default")
      (node (ref "Q2") (pin "C") (pinfunction "C_C") (pintype "passive"))
      (node (ref "Q3") (pin "3") (pinfunction "D_3") (pintype "passive"))
    )
    (net (code "51") (name "Net-(R15-Pad2)") (class "Default")
      (node (ref "R15") (pin "2") (pinfunction "2_2") (pintype "passive"))
      (node (ref "ZD1") (pin "C") (pinfunction "C_C") (pintype "passive"))
    )
    (net (code "52") (name "Net-(X1B-1)") (class "Default")
      (node (ref "B1") (pin "AC1") (pinfunction "AC1_AC1") (pintype "passive"))
      (node (ref "X1") (pin "2") (pinfunction "1_2") (pintype "bidirectional"))
    )
    (net (code "53") (name "OUT+") (class "Default")
      (node (ref "X2") (pin "9") (pinfunction "1_9") (pintype "passive"))
      (node (ref "ZD1") (pin "A") (pinfunction "A_A") (pintype "passive"))
    )
    (net (code "54") (name "PREG_OUT") (class "Default")
      (node (ref "FB1") (pin "2") (pinfunction "2_2") (pintype "passive"))
      (node (ref "X2") (pin "14") (pinfunction "1_14") (pintype "passive"))
      (node (ref "X2") (pin "15") (pinfunction "1_15") (pintype "passive"))
      (node (ref "X2") (pin "16") (pinfunction "1_16") (pintype "passive"))
      (node (ref "X2") (pin "17") (pinfunction "1_17") (pintype "passive"))
    )
    (net (code "55") (name "PRE_OE") (class "Default")
      (node (ref "R2") (pin "1") (pinfunction "1_1") (pintype "passive"))
      (node (ref "X2") (pin "5") (pinfunction "1_5") (pintype "passive"))
    )
    (net (code "56") (name "PWRGOOD") (class "Default")
      (node (ref "IC6") (pin "5") (pinfunction "~{ERROR}_5") (pintype "input"))
      (node (ref "R27") (pin "2") (pinfunction "2_2") (pintype "passive"))
      (node (ref "X2") (pin "1") (pinfunction "1_1") (pintype "passive"))
    )
    (net (code "57") (name "SGND") (class "Default")
      (node (ref "C19") (pin "2") (pinfunction "2_2") (pintype "passive"))
      (node (ref "C21") (pin "2") (pinfunction "2_2") (pintype "passive"))
      (node (ref "C9") (pin "1") (pinfunction "1_1") (pintype "passive"))
      (node (ref "IC1") (pin "3") (pinfunction "SGND_3") (pintype "passive"))
      (node (ref "JMP1") (pin "1") (pinfunction "1_1") (pintype "passive"))
      (node (ref "R16") (pin "2") (pinfunction "2_2") (pintype "passive"))
      (node (ref "R5") (pin "2") (pinfunction "2_2") (pintype "passive"))
      (node (ref "SH1") (pin "P$1") (pinfunction "GND_A_P$1") (pintype "bidirectional"))
    )
    (net (code "58") (name "SYNC") (class "Default")
      (node (ref "IC2") (pin "2") (pinfunction "A1_2") (pintype "input"))
      (node (ref "IC5") (pin "4") (pinfunction "SYNC_4") (pintype "input"))
      (node (ref "JMP1") (pin "3") (pinfunction "3_3") (pintype "passive"))
      (node (ref "X4") (pin "2") (pinfunction "S_2") (pintype "passive"))
    )
    (net (code "59") (name "TEMP_FREQ") (class "Default")
      (node (ref "IC7") (pin "3") (pinfunction "Q_3") (pintype "output"))
      (node (ref "X2") (pin "3") (pinfunction "1_3") (pintype "passive"))
    )
    (net (code "60") (name "V+") (class "Default")
      (node (ref "C29") (pin "1") (pinfunction "1_1") (pintype "passive"))
      (node (ref "D6") (pin "C") (pinfunction "C_C") (pintype "passive"))
      (node (ref "IC4") (pin "1") (pinfunction "VO_1") (pintype "passive"))
      (node (ref "X2") (pin "6") (pinfunction "1_6") (pintype "passive"))
    )
    (net (code "61") (name "V-") (class "Default")
      (node (ref "C26") (pin "2") (pinfunction "2_2") (pintype "passive"))
      (node (ref "D5") (pin "A") (pinfunction "A_A") (pintype "passive"))
      (node (ref "IC3") (pin "1") (pinfunction "OUT_1") (pintype "passive"))
      (node (ref "X2") (pin "4") (pinfunction "1_4") (pintype "passive"))
    )
    (net (code "62") (name "VBIAS") (class "Default")
      (node (ref "C5") (pin "+") (pinfunction "+_+") (pintype "passive"))
      (node (ref "C5") (pin "+.1") (pinfunction "+_+.1") (pintype "passive"))
      (node (ref "D1") (pin "C") (pinfunction "C_C") (pintype "passive"))
      (node (ref "X2") (pin "18") (pinfunction "1_18") (pintype "passive"))
    )
    (net (code "63") (name "unconnected-(IC1-PGOOD-Pad7)") (class "Default")
      (node (ref "IC1") (pin "7") (pinfunction "PGOOD_7") (pintype "output"))
    )
    (net (code "64") (name "unconnected-(IC6-SD-Pad3)") (class "Default")
      (node (ref "IC6") (pin "3") (pinfunction "SD_3") (pintype "input"))
    )
    (net (code "65") (name "unconnected-(IC6-SENSE-Pad2)") (class "Default")
      (node (ref "IC6") (pin "2") (pinfunction "SENSE_2") (pintype "input"))
    )
    (net (code "66") (name "unconnected-(IC6-VTAP-Pad6)") (class "Default")
      (node (ref "IC6") (pin "6") (pinfunction "VTAP_6") (pintype "input"))
    )
    (net (code "67") (name "unconnected-(IC7-CV-Pad5)") (class "Default")
      (node (ref "IC7") (pin "5") (pinfunction "CV_5") (pintype "input"))
    )
    (net (code "68") (name "~{SET_100%}") (class "Default")
      (node (ref "Q3") (pin "1") (pinfunction "G_1") (pintype "passive"))
      (node (ref "X2") (pin "7") (pinfunction "1_7") (pintype "passive"))
    )
  )
)
